# MCU.net
KiCad netlist of a schematic drawn in Altium Designer
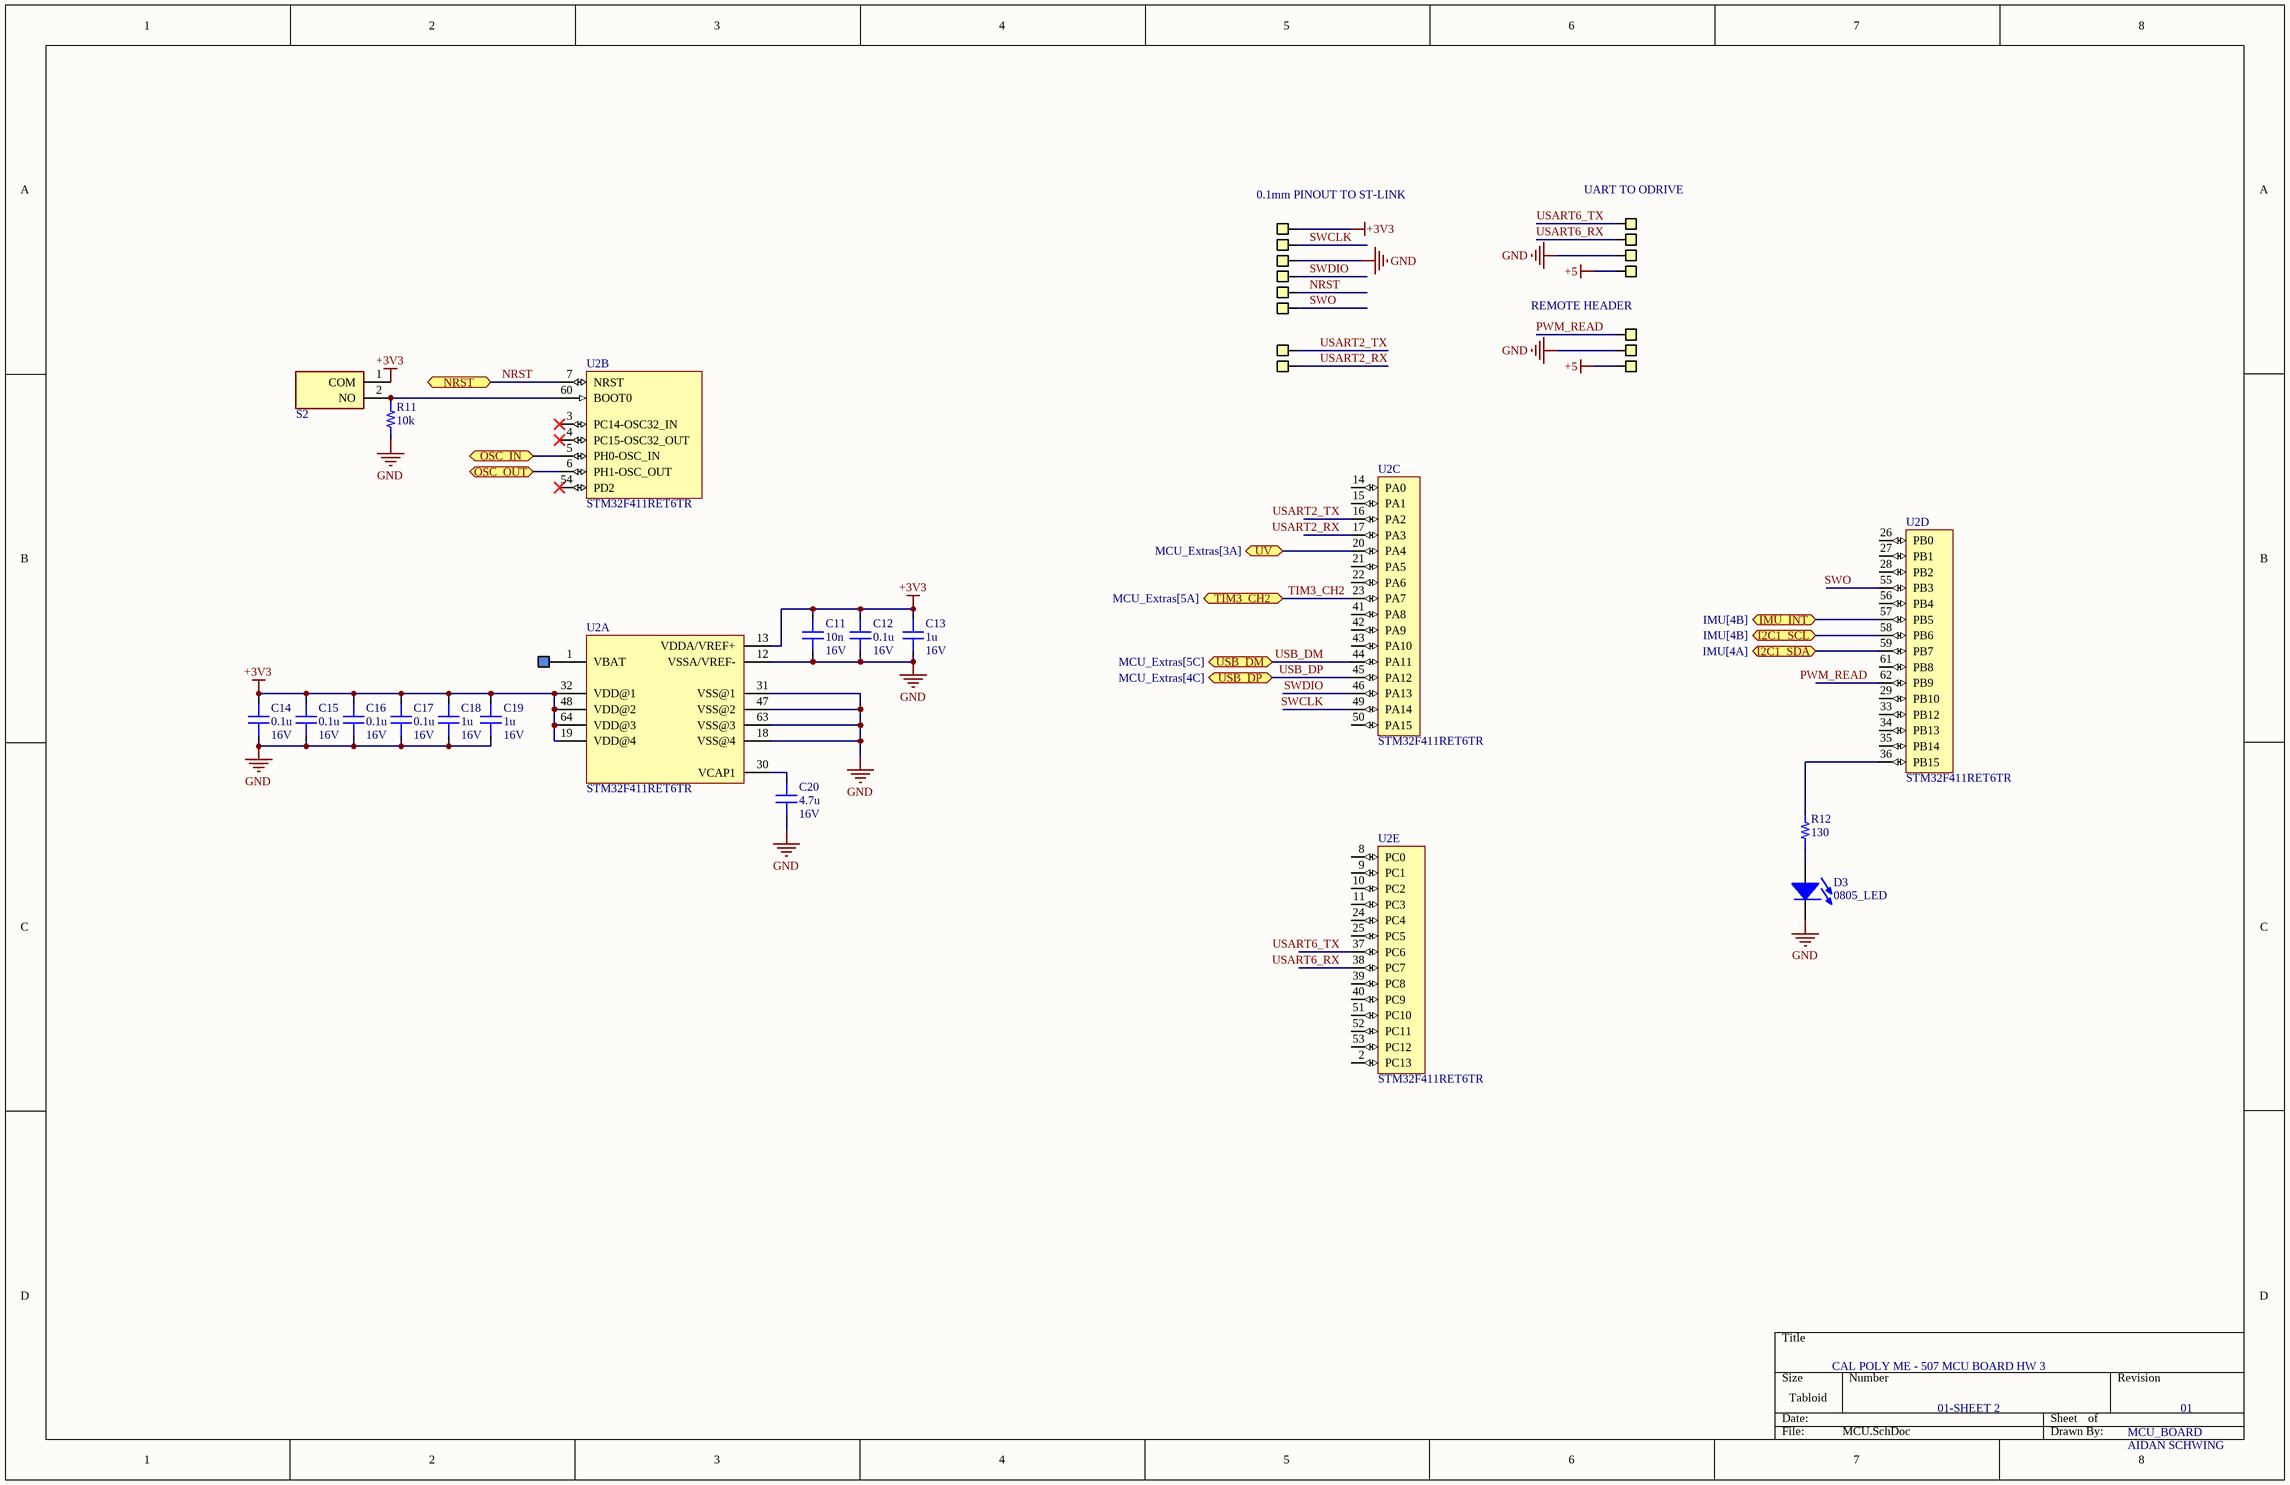
[diagram p0: MCU.SchDoc]

(export (version "E")
  (design (tool "Eeschema 10.0.6"))
  (components
    (comp (ref "C11")
      (value "10n")
      (footprint "0805_CAP")
      (fields (field (name "VOLTAGE") "16V") (field (name "Comment") "Capacitor"))
      (libsource (lib "Capacitors") (part "Capacitor"))
    )
    (comp (ref "C12")
      (value "0.1u")
      (footprint "0805_CAP")
      (fields (field (name "VOLTAGE") "16V") (field (name "Comment") "Capacitor"))
      (libsource (lib "Capacitors") (part "Capacitor"))
    )
    (comp (ref "C13")
      (value "1u")
      (footprint "0805_CAP")
      (fields (field (name "VOLTAGE") "16V") (field (name "Comment") "Capacitor"))
      (libsource (lib "Capacitors") (part "Capacitor"))
    )
    (comp (ref "C14")
      (value "0.1u")
      (footprint "0805_CAP")
      (fields (field (name "VOLTAGE") "16V") (field (name "Comment") "Capacitor"))
      (libsource (lib "Capacitors") (part "Capacitor"))
    )
    (comp (ref "C15")
      (value "0.1u")
      (footprint "0805_CAP")
      (fields (field (name "VOLTAGE") "16V") (field (name "Comment") "Capacitor"))
      (libsource (lib "Capacitors") (part "Capacitor"))
    )
    (comp (ref "C16")
      (value "0.1u")
      (footprint "0805_CAP")
      (fields (field (name "VOLTAGE") "16V") (field (name "Comment") "Capacitor"))
      (libsource (lib "Capacitors") (part "Capacitor"))
    )
    (comp (ref "C17")
      (value "0.1u")
      (footprint "0805_CAP")
      (fields (field (name "VOLTAGE") "16V") (field (name "Comment") "Capacitor"))
      (libsource (lib "Capacitors") (part "Capacitor"))
    )
    (comp (ref "C18")
      (value "1u")
      (footprint "0805_CAP")
      (fields (field (name "VOLTAGE") "16V") (field (name "Comment") "Capacitor"))
      (libsource (lib "Capacitors") (part "Capacitor"))
    )
    (comp (ref "C19")
      (value "1u")
      (footprint "0805_CAP")
      (fields (field (name "VOLTAGE") "16V") (field (name "Comment") "Capacitor"))
      (libsource (lib "Capacitors") (part "Capacitor"))
    )
    (comp (ref "C20")
      (value "4.7u")
      (footprint "0805_CAP")
      (fields (field (name "VOLTAGE") "16V") (field (name "Comment") "Capacitor"))
      (libsource (lib "Capacitors") (part "Capacitor"))
    )
    (comp (ref "D3")
      (value "0805_LED")
      (footprint "0805_LED")
      (description "Generic 0805 LED")
      (libsource (lib "Diodes") (part "0805_LED"))
    )
    (comp (ref "R11")
      (value "10k")
      (footprint "0603_RES")
      (fields (field (name "Comment") "Resistor"))
      (libsource (lib "Resistors") (part "Resistor"))
    )
    (comp (ref "R12")
      (value "130")
      (footprint "0603_RES")
      (fields (field (name "Comment") "Resistor"))
      (libsource (lib "Resistors") (part "Resistor"))
    )
    (comp (ref "S2")
      (value "DS04-254-2-01BK-SMT-TR")
      (footprint "DS04254201BKSMTTR")
      (fields (field (name "MOUSER PART NUMBER") "490-DS04254201BK-STR"))
      (libsource (lib "ElectroMechanical") (part "DS04-254-2-01BK-SMT-TR"))
    )
    (comp (ref "U2")
      (value "STM32F411RET6TR")
      (footprint "507_Part_Footprints:QFP50P1200X1200X160-64N")
      (fields (field (name "MF") "{'manufacturer': u'STMicroelectronics'}"))
      (libsource (lib "507_Parts") (part "STM32F411RET6TR"))
    )
    (comp (ref "X6")
      (value "GenericPinHeader(0.1in)")
      (footprint "GenericPinHeader(.1in)")
      (description "Generic .1in(2.54mm) pitch pin header")
      (libsource (lib "Connectors") (part "GenericPinHeader(0.1in)"))
    )
    (comp (ref "X7")
      (value "GenericPinHeader(0.1in)")
      (footprint "GenericPinHeader(.1in)")
      (description "Generic .1in(2.54mm) pitch pin header")
      (libsource (lib "") (part "GenericPinHeader(0.1in)_1"))
    )
    (comp (ref "X8")
      (value "GenericPinHeader(0.1in)")
      (footprint "GenericPinHeader(.1in)")
      (description "Generic .1in(2.54mm) pitch pin header")
      (libsource (lib "") (part "GenericPinHeader(0.1in)_1"))
    )
    (comp (ref "X9")
      (value "GenericPinHeader(0.1in)")
      (footprint "GenericPinHeader(.1in)")
      (description "Generic .1in(2.54mm) pitch pin header")
      (libsource (lib "Connectors") (part "GenericPinHeader(0.1in)"))
    )
    (comp (ref "X10")
      (value "GenericPinHeader(0.1in)")
      (footprint "GenericPinHeader(.1in)")
      (description "Generic .1in(2.54mm) pitch pin header")
      (libsource (lib "") (part "GenericPinHeader(0.1in)_1"))
    )
    (comp (ref "X12")
      (value "GenericPinHeader(0.1in)")
      (footprint "GenericPinHeader(.1in)")
      (description "Generic .1in(2.54mm) pitch pin header")
      (libsource (lib "") (part "GenericPinHeader(0.1in)_1"))
    )
    (comp (ref "X13")
      (value "GenericPinHeader(0.1in)")
      (footprint "GenericPinHeader(.1in)")
      (description "Generic .1in(2.54mm) pitch pin header")
      (libsource (lib "") (part "GenericPinHeader(0.1in)_1"))
    )
    (comp (ref "X14")
      (value "GenericPinHeader(0.1in)")
      (footprint "GenericPinHeader(.1in)")
      (description "Generic .1in(2.54mm) pitch pin header")
      (libsource (lib "") (part "GenericPinHeader(0.1in)_1"))
    )
    (comp (ref "X15")
      (value "GenericPinHeader(0.1in)")
      (footprint "GenericPinHeader(.1in)")
      (description "Generic .1in(2.54mm) pitch pin header")
      (libsource (lib "") (part "GenericPinHeader(0.1in)_1"))
    )
    (comp (ref "X16")
      (value "GenericPinHeader(0.1in)")
      (footprint "GenericPinHeader(.1in)")
      (description "Generic .1in(2.54mm) pitch pin header")
      (libsource (lib "") (part "GenericPinHeader(0.1in)_1"))
    )
    (comp (ref "X17")
      (value "HeaderPad")
      (footprint "HeaderPad")
      (description "Pad for pin header")
      (libsource (lib "Connectors") (part "HeaderPad"))
    )
    (comp (ref "X18")
      (value "GenericPinHeader(0.1in)")
      (footprint "GenericPinHeader(.1in)")
      (description "Generic .1in(2.54mm) pitch pin header")
      (libsource (lib "Connectors") (part "GenericPinHeader(0.1in)"))
    )
    (comp (ref "X20")
      (value "GenericPinHeader(0.1in)")
      (footprint "GenericPinHeader(.1in)")
      (description "Generic .1in(2.54mm) pitch pin header")
      (libsource (lib "Connectors") (part "GenericPinHeader(0.1in)"))
    )
    (comp (ref "X21")
      (value "GenericPinHeader(0.1in)")
      (footprint "GenericPinHeader(.1in)")
      (description "Generic .1in(2.54mm) pitch pin header")
      (libsource (lib "Connectors") (part "GenericPinHeader(0.1in)"))
    )
    (comp (ref "X24")
      (value "GenericPinHeader(0.1in)")
      (footprint "GenericPinHeader(.1in)")
      (description "Generic .1in(2.54mm) pitch pin header")
      (libsource (lib "Connectors") (part "GenericPinHeader(0.1in)"))
    )
    (comp (ref "X25")
      (value "GenericPinHeader(0.1in)")
      (footprint "GenericPinHeader(.1in)")
      (description "Generic .1in(2.54mm) pitch pin header")
      (libsource (lib "Connectors") (part "GenericPinHeader(0.1in)"))
    )
  )
  (nets
    (net (code "1") (name "+3V3") (class "Default")
      (node (ref "C11") (pin "1") (pinfunction "1_1") (pintype "passive"))
      (node (ref "C12") (pin "1") (pinfunction "1_1") (pintype "passive"))
      (node (ref "C13") (pin "1") (pinfunction "1_1") (pintype "passive"))
      (node (ref "C14") (pin "1") (pinfunction "1_1") (pintype "passive"))
      (node (ref "C15") (pin "1") (pinfunction "1_1") (pintype "passive"))
      (node (ref "C16") (pin "1") (pinfunction "1_1") (pintype "passive"))
      (node (ref "C17") (pin "1") (pinfunction "1_1") (pintype "passive"))
      (node (ref "C18") (pin "1") (pinfunction "1_1") (pintype "passive"))
      (node (ref "C19") (pin "1") (pinfunction "1_1") (pintype "passive"))
      (node (ref "S2") (pin "1") (pinfunction "COM_1") (pintype "passive"))
      (node (ref "U2") (pin "13") (pinfunction "VDDA/VREF+_13") (pintype "power_in"))
      (node (ref "U2") (pin "19") (pinfunction "VDD@4_19") (pintype "power_in"))
      (node (ref "U2") (pin "32") (pinfunction "VDD@1_32") (pintype "power_in"))
      (node (ref "U2") (pin "48") (pinfunction "VDD@2_48") (pintype "power_in"))
      (node (ref "U2") (pin "64") (pinfunction "VDD@3_64") (pintype "power_in"))
      (node (ref "X7") (pin "1") (pinfunction "Pin_1") (pintype "passive"))
    )
    (net (code "2") (name "+5") (class "Default")
      (node (ref "X21") (pin "1") (pinfunction "Pin_1") (pintype "passive"))
      (node (ref "X25") (pin "1") (pinfunction "Pin_1") (pintype "passive"))
    )
    (net (code "3") (name "/I2C1_SCL") (class "Default")
      (node (ref "U2") (pin "58") (pinfunction "PB6_58") (pintype "bidirectional"))
    )
    (net (code "4") (name "/I2C1_SDA") (class "Default")
      (node (ref "U2") (pin "59") (pinfunction "PB7_59") (pintype "bidirectional"))
    )
    (net (code "5") (name "/IMU_INT") (class "Default")
      (node (ref "U2") (pin "57") (pinfunction "PB5_57") (pintype "bidirectional"))
    )
    (net (code "6") (name "/NRST") (class "Default")
      (node (ref "U2") (pin "7") (pinfunction "NRST_7") (pintype "bidirectional"))
      (node (ref "X13") (pin "1") (pinfunction "Pin_1") (pintype "passive"))
    )
    (net (code "7") (name "/OSC_IN") (class "Default")
      (node (ref "U2") (pin "5") (pinfunction "PH0-OSC_IN_5") (pintype "bidirectional"))
    )
    (net (code "8") (name "/OSC_OUT") (class "Default")
      (node (ref "U2") (pin "6") (pinfunction "PH1-OSC_OUT_6") (pintype "bidirectional"))
    )
    (net (code "9") (name "/PWM_READ") (class "Default")
      (node (ref "U2") (pin "62") (pinfunction "PB9_62") (pintype "bidirectional"))
      (node (ref "X18") (pin "1") (pinfunction "Pin_1") (pintype "passive"))
    )
    (net (code "10") (name "/SWCLK") (class "Default")
      (node (ref "U2") (pin "49") (pinfunction "PA14_49") (pintype "bidirectional"))
      (node (ref "X8") (pin "1") (pinfunction "Pin_1") (pintype "passive"))
    )
    (net (code "11") (name "/SWDIO") (class "Default")
      (node (ref "U2") (pin "46") (pinfunction "PA13_46") (pintype "bidirectional"))
      (node (ref "X12") (pin "1") (pinfunction "Pin_1") (pintype "passive"))
    )
    (net (code "12") (name "/SWO") (class "Default")
      (node (ref "U2") (pin "55") (pinfunction "PB3_55") (pintype "bidirectional"))
      (node (ref "X14") (pin "1") (pinfunction "Pin_1") (pintype "passive"))
    )
    (net (code "13") (name "/TIM3_CH2") (class "Default")
      (node (ref "U2") (pin "23") (pinfunction "PA7_23") (pintype "bidirectional"))
    )
    (net (code "14") (name "/USART2_RX") (class "Default")
      (node (ref "U2") (pin "17") (pinfunction "PA3_17") (pintype "bidirectional"))
      (node (ref "X16") (pin "1") (pinfunction "Pin_1") (pintype "passive"))
    )
    (net (code "15") (name "/USART2_TX") (class "Default")
      (node (ref "U2") (pin "16") (pinfunction "PA2_16") (pintype "bidirectional"))
      (node (ref "X15") (pin "1") (pinfunction "Pin_1") (pintype "passive"))
    )
    (net (code "16") (name "/USART6_RX") (class "Default")
      (node (ref "U2") (pin "38") (pinfunction "PC7_38") (pintype "bidirectional"))
      (node (ref "X9") (pin "1") (pinfunction "Pin_1") (pintype "passive"))
    )
    (net (code "17") (name "/USART6_TX") (class "Default")
      (node (ref "U2") (pin "37") (pinfunction "PC6_37") (pintype "bidirectional"))
      (node (ref "X6") (pin "1") (pinfunction "Pin_1") (pintype "passive"))
    )
    (net (code "18") (name "/USB_DM") (class "Default")
      (node (ref "U2") (pin "44") (pinfunction "PA11_44") (pintype "bidirectional"))
    )
    (net (code "19") (name "/USB_DP") (class "Default")
      (node (ref "U2") (pin "45") (pinfunction "PA12_45") (pintype "bidirectional"))
    )
    (net (code "20") (name "/~{UV}") (class "Default")
      (node (ref "U2") (pin "20") (pinfunction "PA4_20") (pintype "bidirectional"))
    )
    (net (code "21") (name "GND") (class "Default")
      (node (ref "C11") (pin "2") (pinfunction "2_2") (pintype "passive"))
      (node (ref "C12") (pin "2") (pinfunction "2_2") (pintype "passive"))
      (node (ref "C13") (pin "2") (pinfunction "2_2") (pintype "passive"))
      (node (ref "C14") (pin "2") (pinfunction "2_2") (pintype "passive"))
      (node (ref "C15") (pin "2") (pinfunction "2_2") (pintype "passive"))
      (node (ref "C16") (pin "2") (pinfunction "2_2") (pintype "passive"))
      (node (ref "C17") (pin "2") (pinfunction "2_2") (pintype "passive"))
      (node (ref "C18") (pin "2") (pinfunction "2_2") (pintype "passive"))
      (node (ref "C19") (pin "2") (pinfunction "2_2") (pintype "passive"))
      (node (ref "C20") (pin "2") (pinfunction "2_2") (pintype "passive"))
      (node (ref "D3") (pin "2") (pinfunction "K_2") (pintype "passive"))
      (node (ref "R11") (pin "1") (pinfunction "1_1") (pintype "passive"))
      (node (ref "U2") (pin "12") (pinfunction "VSSA/VREF-_12") (pintype "power_in"))
      (node (ref "U2") (pin "18") (pinfunction "VSS@4_18") (pintype "power_in"))
      (node (ref "U2") (pin "31") (pinfunction "VSS@1_31") (pintype "power_in"))
      (node (ref "U2") (pin "47") (pinfunction "VSS@2_47") (pintype "power_in"))
      (node (ref "U2") (pin "63") (pinfunction "VSS@3_63") (pintype "power_in"))
      (node (ref "X10") (pin "1") (pinfunction "Pin_1") (pintype "passive"))
      (node (ref "X20") (pin "1") (pinfunction "Pin_1") (pintype "passive"))
      (node (ref "X24") (pin "1") (pinfunction "Pin_1") (pintype "passive"))
    )
    (net (code "22") (name "Net-(D3-A)") (class "Default")
      (node (ref "D3") (pin "1") (pinfunction "A_1") (pintype "passive"))
      (node (ref "R12") (pin "1") (pinfunction "1_1") (pintype "passive"))
    )
    (net (code "23") (name "Net-(S2-NO)") (class "Default")
      (node (ref "R11") (pin "2") (pinfunction "2_2") (pintype "passive"))
      (node (ref "S2") (pin "2") (pinfunction "NO_2") (pintype "passive"))
      (node (ref "U2") (pin "60") (pinfunction "BOOT0_60") (pintype "input"))
    )
    (net (code "24") (name "Net-(U2A-VBAT)") (class "Default")
      (node (ref "U2") (pin "1") (pinfunction "VBAT_1") (pintype "power_in"))
      (node (ref "X17") (pin "1") (pinfunction "Pin_1") (pintype "passive"))
    )
    (net (code "25") (name "Net-(U2A-VCAP1)") (class "Default")
      (node (ref "C20") (pin "1") (pinfunction "1_1") (pintype "passive"))
      (node (ref "U2") (pin "30") (pinfunction "VCAP1_30") (pintype "passive"))
    )
    (net (code "26") (name "Net-(U2D-PB15)") (class "Default")
      (node (ref "R12") (pin "2") (pinfunction "2_2") (pintype "passive"))
      (node (ref "U2") (pin "36") (pinfunction "PB15_36") (pintype "bidirectional"))
    )
    (net (code "27") (name "unconnected-(U2B-PC14-OSC32_IN-Pad3)") (class "Default")
      (node (ref "U2") (pin "3") (pinfunction "PC14-OSC32_IN_3") (pintype "bidirectional+no_connect"))
    )
    (net (code "28") (name "unconnected-(U2B-PC15-OSC32_OUT-Pad4)") (class "Default")
      (node (ref "U2") (pin "4") (pinfunction "PC15-OSC32_OUT_4") (pintype "bidirectional+no_connect"))
    )
    (net (code "29") (name "unconnected-(U2B-PD2-Pad54)") (class "Default")
      (node (ref "U2") (pin "54") (pinfunction "PD2_54") (pintype "bidirectional+no_connect"))
    )
    (net (code "30") (name "unconnected-(U2C-PA0-Pad14)") (class "Default")
      (node (ref "U2") (pin "14") (pinfunction "PA0_14") (pintype "bidirectional"))
    )
    (net (code "31") (name "unconnected-(U2C-PA1-Pad15)") (class "Default")
      (node (ref "U2") (pin "15") (pinfunction "PA1_15") (pintype "bidirectional"))
    )
    (net (code "32") (name "unconnected-(U2C-PA5-Pad21)") (class "Default")
      (node (ref "U2") (pin "21") (pinfunction "PA5_21") (pintype "bidirectional"))
    )
    (net (code "33") (name "unconnected-(U2C-PA6-Pad22)") (class "Default")
      (node (ref "U2") (pin "22") (pinfunction "PA6_22") (pintype "bidirectional"))
    )
    (net (code "34") (name "unconnected-(U2C-PA8-Pad41)") (class "Default")
      (node (ref "U2") (pin "41") (pinfunction "PA8_41") (pintype "bidirectional"))
    )
    (net (code "35") (name "unconnected-(U2C-PA9-Pad42)") (class "Default")
      (node (ref "U2") (pin "42") (pinfunction "PA9_42") (pintype "bidirectional"))
    )
    (net (code "36") (name "unconnected-(U2C-PA10-Pad43)") (class "Default")
      (node (ref "U2") (pin "43") (pinfunction "PA10_43") (pintype "bidirectional"))
    )
    (net (code "37") (name "unconnected-(U2C-PA15-Pad50)") (class "Default")
      (node (ref "U2") (pin "50") (pinfunction "PA15_50") (pintype "bidirectional"))
    )
    (net (code "38") (name "unconnected-(U2D-PB0-Pad26)") (class "Default")
      (node (ref "U2") (pin "26") (pinfunction "PB0_26") (pintype "bidirectional"))
    )
    (net (code "39") (name "unconnected-(U2D-PB1-Pad27)") (class "Default")
      (node (ref "U2") (pin "27") (pinfunction "PB1_27") (pintype "bidirectional"))
    )
    (net (code "40") (name "unconnected-(U2D-PB2-Pad28)") (class "Default")
      (node (ref "U2") (pin "28") (pinfunction "PB2_28") (pintype "bidirectional"))
    )
    (net (code "41") (name "unconnected-(U2D-PB4-Pad56)") (class "Default")
      (node (ref "U2") (pin "56") (pinfunction "PB4_56") (pintype "bidirectional"))
    )
    (net (code "42") (name "unconnected-(U2D-PB8-Pad61)") (class "Default")
      (node (ref "U2") (pin "61") (pinfunction "PB8_61") (pintype "bidirectional"))
    )
    (net (code "43") (name "unconnected-(U2D-PB10-Pad29)") (class "Default")
      (node (ref "U2") (pin "29") (pinfunction "PB10_29") (pintype "bidirectional"))
    )
    (net (code "44") (name "unconnected-(U2D-PB12-Pad33)") (class "Default")
      (node (ref "U2") (pin "33") (pinfunction "PB12_33") (pintype "bidirectional"))
    )
    (net (code "45") (name "unconnected-(U2D-PB13-Pad34)") (class "Default")
      (node (ref "U2") (pin "34") (pinfunction "PB13_34") (pintype "bidirectional"))
    )
    (net (code "46") (name "unconnected-(U2D-PB14-Pad35)") (class "Default")
      (node (ref "U2") (pin "35") (pinfunction "PB14_35") (pintype "bidirectional"))
    )
    (net (code "47") (name "unconnected-(U2E-PC0-Pad8)") (class "Default")
      (node (ref "U2") (pin "8") (pinfunction "PC0_8") (pintype "bidirectional"))
    )
    (net (code "48") (name "unconnected-(U2E-PC1-Pad9)") (class "Default")
      (node (ref "U2") (pin "9") (pinfunction "PC1_9") (pintype "bidirectional"))
    )
    (net (code "49") (name "unconnected-(U2E-PC2-Pad10)") (class "Default")
      (node (ref "U2") (pin "10") (pinfunction "PC2_10") (pintype "bidirectional"))
    )
    (net (code "50") (name "unconnected-(U2E-PC3-Pad11)") (class "Default")
      (node (ref "U2") (pin "11") (pinfunction "PC3_11") (pintype "bidirectional"))
    )
    (net (code "51") (name "unconnected-(U2E-PC4-Pad24)") (class "Default")
      (node (ref "U2") (pin "24") (pinfunction "PC4_24") (pintype "bidirectional"))
    )
    (net (code "52") (name "unconnected-(U2E-PC5-Pad25)") (class "Default")
      (node (ref "U2") (pin "25") (pinfunction "PC5_25") (pintype "bidirectional"))
    )
    (net (code "53") (name "unconnected-(U2E-PC8-Pad39)") (class "Default")
      (node (ref "U2") (pin "39") (pinfunction "PC8_39") (pintype "bidirectional"))
    )
    (net (code "54") (name "unconnected-(U2E-PC9-Pad40)") (class "Default")
      (node (ref "U2") (pin "40") (pinfunction "PC9_40") (pintype "bidirectional"))
    )
    (net (code "55") (name "unconnected-(U2E-PC10-Pad51)") (class "Default")
      (node (ref "U2") (pin "51") (pinfunction "PC10_51") (pintype "bidirectional"))
    )
    (net (code "56") (name "unconnected-(U2E-PC11-Pad52)") (class "Default")
      (node (ref "U2") (pin "52") (pinfunction "PC11_52") (pintype "bidirectional"))
    )
    (net (code "57") (name "unconnected-(U2E-PC12-Pad53)") (class "Default")
      (node (ref "U2") (pin "53") (pinfunction "PC12_53") (pintype "bidirectional"))
    )
    (net (code "58") (name "unconnected-(U2E-PC13-Pad2)") (class "Default")
      (node (ref "U2") (pin "2") (pinfunction "PC13_2") (pintype "bidirectional"))
    )
  )
)
